# Astable_555_Timer.net
KiCad netlist of a schematic drawn in EAGLE
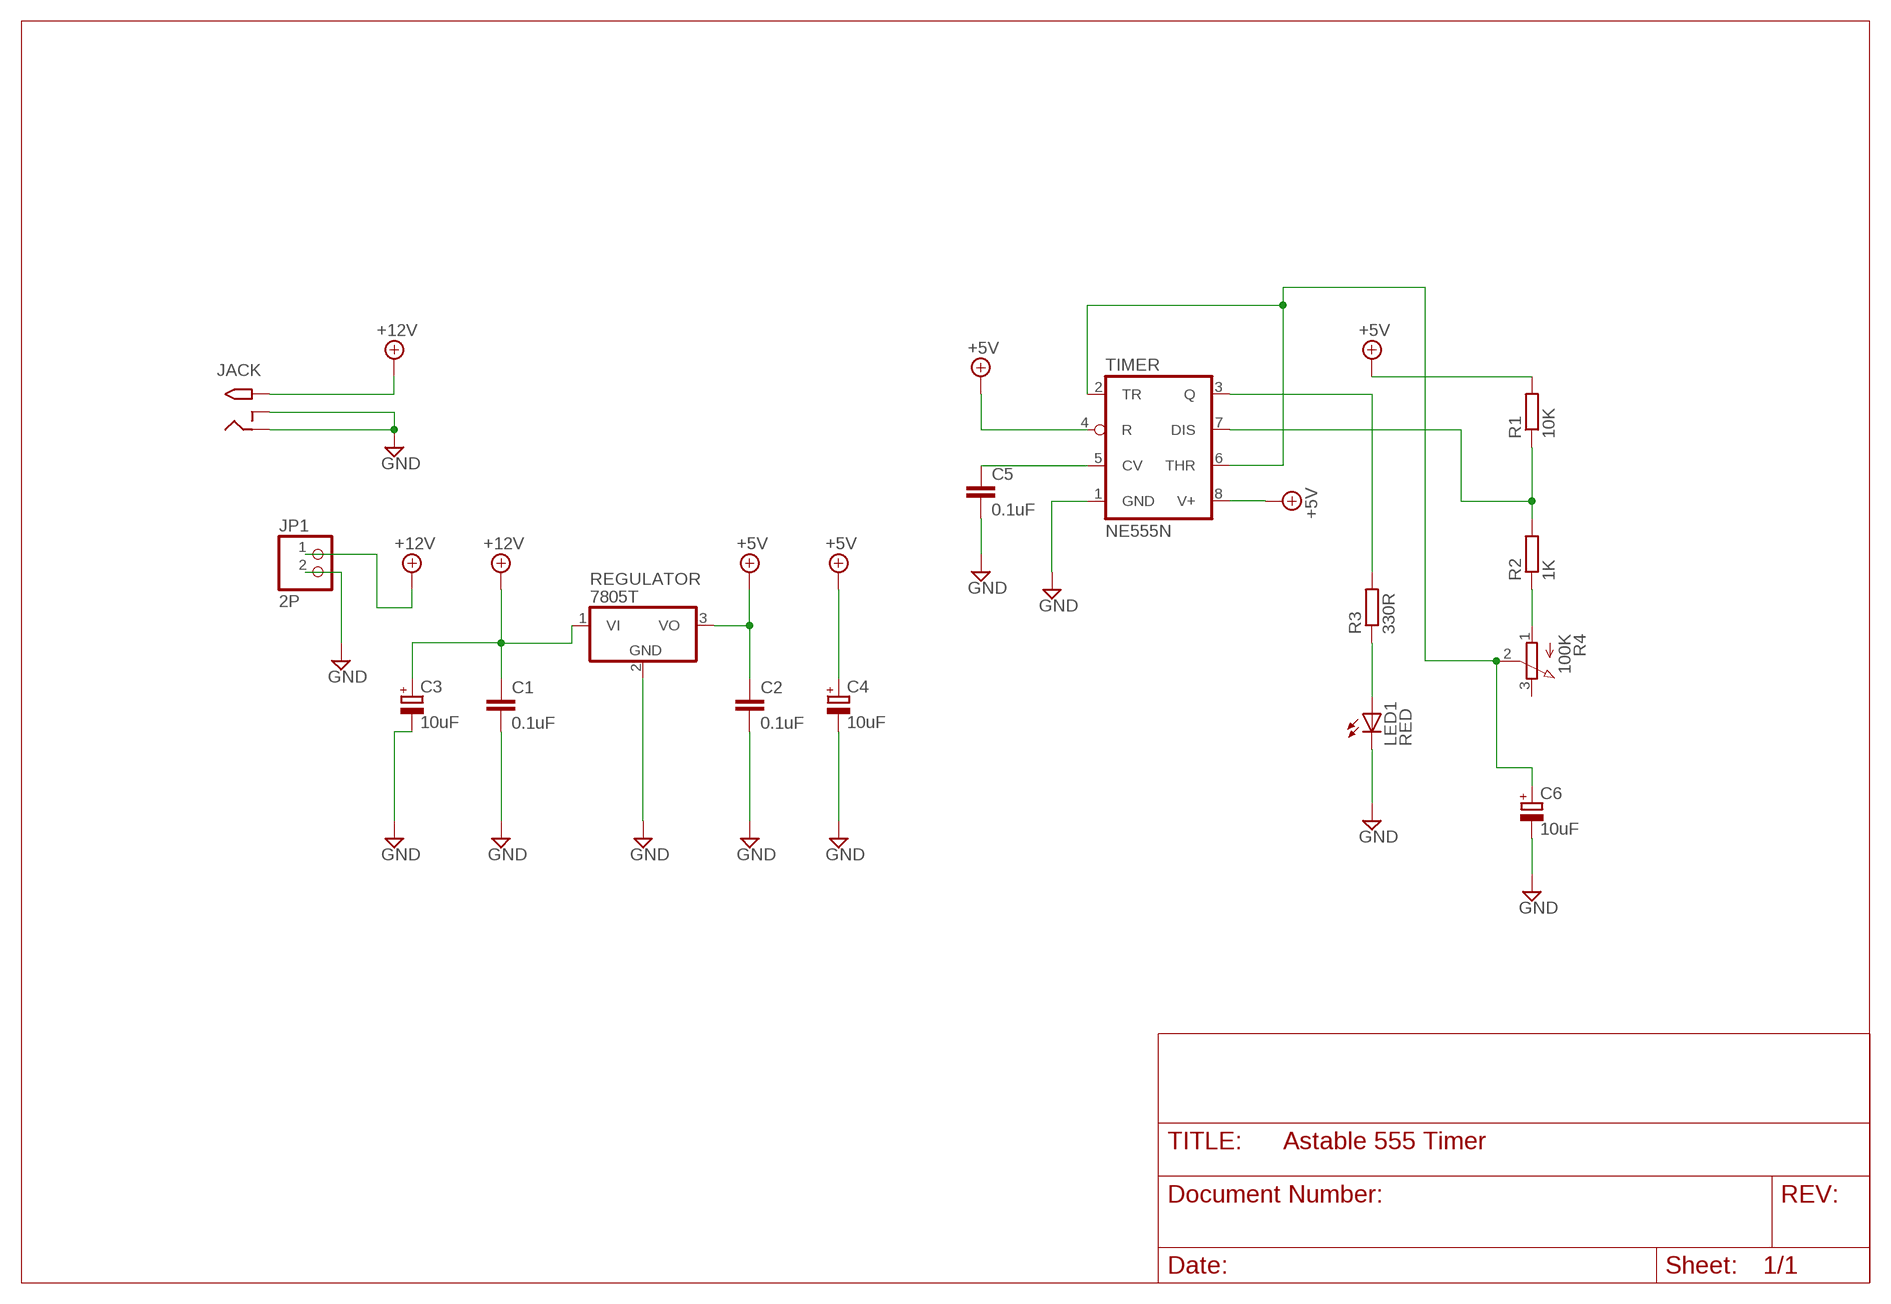
[diagram p0: schematic, sheet 1]

(export (version "E")
  (design (tool "Eeschema 10.0.6"))
  (components
    (comp (ref "C1")
      (value "0.1uF")
      (footprint "eagle-import:C050-035X075")
      (libsource (lib "eagle-import") (part "C-EU050-035X075"))
    )
    (comp (ref "C2")
      (value "0.1uF")
      (footprint "eagle-import:C050-035X075")
      (libsource (lib "eagle-import") (part "C-EU050-035X075"))
    )
    (comp (ref "C3")
      (value "10uF")
      (footprint "eagle-import:E3,5-8")
      (libsource (lib "eagle-import") (part "CPOL-EUE3.5-8"))
    )
    (comp (ref "C4")
      (value "10uF")
      (footprint "eagle-import:E3,5-8")
      (libsource (lib "eagle-import") (part "CPOL-EUE3.5-8"))
    )
    (comp (ref "C5")
      (value "0.1uF")
      (footprint "eagle-import:C050-035X075")
      (libsource (lib "eagle-import") (part "C-EU050-035X075"))
    )
    (comp (ref "C6")
      (value "10uF")
      (footprint "eagle-import:E3,5-8")
      (libsource (lib "eagle-import") (part "CPOL-EUE3.5-8"))
    )
    (comp (ref "JACK")
      (value "2.1MMJACKTHM")
      (footprint "eagle-import:PJ-102A")
      (libsource (lib "eagle-import") (part "2.1MMJACKTHM"))
    )
    (comp (ref "JP1")
      (value "2P")
      (footprint "eagle-import:1X02")
      (libsource (lib "eagle-import") (part "PINHD-1X2"))
    )
    (comp (ref "LED1")
      (value "RED")
      (footprint "eagle-import:LED5MM")
      (libsource (lib "eagle-import") (part "LED5MM"))
    )
    (comp (ref "R1")
      (value "10K")
      (footprint "eagle-import:0207_15")
      (libsource (lib "eagle-import") (part "R-EU_0207/15"))
    )
    (comp (ref "R2")
      (value "1K")
      (footprint "eagle-import:0207_15")
      (libsource (lib "eagle-import") (part "R-EU_0207/15"))
    )
    (comp (ref "R3")
      (value "330R")
      (footprint "eagle-import:0207_15")
      (libsource (lib "eagle-import") (part "R-EU_0207/15"))
    )
    (comp (ref "R4")
      (value "100K")
      (footprint "eagle-import:3RP_1610N")
      (libsource (lib "eagle-import") (part "3RP/1610N"))
    )
    (comp (ref "REGULATOR")
      (value "7805T")
      (footprint "eagle-import:TO220H")
      (libsource (lib "eagle-import") (part "78T05"))
    )
    (comp (ref "TIMER")
      (value "NE555N")
      (footprint "eagle-import:DIL08-ROUND")
      (libsource (lib "eagle-import") (part "555NNE"))
    )
  )
  (nets
    (net (code "1") (name "+5V") (class "Default")
      (node (ref "C2") (pin "1") (pinfunction "1_1") (pintype "passive"))
      (node (ref "C4") (pin "+") (pinfunction "+_+") (pintype "passive"))
      (node (ref "R1") (pin "2") (pinfunction "2_2") (pintype "passive"))
      (node (ref "REGULATOR") (pin "3") (pinfunction "VO_3") (pintype "passive"))
      (node (ref "TIMER") (pin "4") (pinfunction "R_4") (pintype "input"))
      (node (ref "TIMER") (pin "8") (pinfunction "V+_8") (pintype "power_in"))
    )
    (net (code "2") (name "+12V") (class "Default")
      (node (ref "C1") (pin "1") (pinfunction "1_1") (pintype "passive"))
      (node (ref "C3") (pin "+") (pinfunction "+_+") (pintype "passive"))
      (node (ref "JACK") (pin "TIP") (pinfunction "TIP_TIP") (pintype "bidirectional"))
      (node (ref "JP1") (pin "1") (pinfunction "1_1") (pintype "passive"))
      (node (ref "REGULATOR") (pin "1") (pinfunction "VI_1") (pintype "input"))
    )
    (net (code "3") (name "GND") (class "Default")
      (node (ref "C1") (pin "2") (pinfunction "2_2") (pintype "passive"))
      (node (ref "C2") (pin "2") (pinfunction "2_2") (pintype "passive"))
      (node (ref "C3") (pin "-") (pinfunction "-_-") (pintype "passive"))
      (node (ref "C4") (pin "-") (pinfunction "-_-") (pintype "passive"))
      (node (ref "C5") (pin "2") (pinfunction "2_2") (pintype "passive"))
      (node (ref "C6") (pin "-") (pinfunction "-_-") (pintype "passive"))
      (node (ref "JACK") (pin "RING") (pinfunction "RING_RING") (pintype "bidirectional"))
      (node (ref "JACK") (pin "RING_SW") (pinfunction "RING_SW_RING_SW") (pintype "bidirectional"))
      (node (ref "JP1") (pin "2") (pinfunction "2_2") (pintype "passive"))
      (node (ref "LED1") (pin "K") (pinfunction "C_K") (pintype "passive"))
      (node (ref "REGULATOR") (pin "2") (pinfunction "GND_2") (pintype "passive"))
      (node (ref "TIMER") (pin "1") (pinfunction "GND_1") (pintype "power_in"))
    )
    (net (code "4") (name "Net-(LED1-PadA)") (class "Default")
      (node (ref "LED1") (pin "A") (pinfunction "A_A") (pintype "passive"))
      (node (ref "R3") (pin "1") (pinfunction "1_1") (pintype "passive"))
    )
    (net (code "5") (name "Net-(R4-A)") (class "Default")
      (node (ref "R2") (pin "1") (pinfunction "1_1") (pintype "passive"))
      (node (ref "R4") (pin "1") (pinfunction "A_1") (pintype "passive"))
    )
    (net (code "6") (name "Net-(R4-S)") (class "Default")
      (node (ref "C6") (pin "+") (pinfunction "+_+") (pintype "passive"))
      (node (ref "R4") (pin "2") (pinfunction "S_2") (pintype "passive"))
      (node (ref "TIMER") (pin "2") (pinfunction "TR_2") (pintype "input"))
      (node (ref "TIMER") (pin "6") (pinfunction "THR_6") (pintype "input"))
    )
    (net (code "7") (name "Net-(TIMER-CV)") (class "Default")
      (node (ref "C5") (pin "1") (pinfunction "1_1") (pintype "passive"))
      (node (ref "TIMER") (pin "5") (pinfunction "CV_5") (pintype "input"))
    )
    (net (code "8") (name "Net-(TIMER-DIS)") (class "Default")
      (node (ref "R1") (pin "1") (pinfunction "1_1") (pintype "passive"))
      (node (ref "R2") (pin "2") (pinfunction "2_2") (pintype "passive"))
      (node (ref "TIMER") (pin "7") (pinfunction "DIS_7") (pintype "input"))
    )
    (net (code "9") (name "Net-(TIMER-Q)") (class "Default")
      (node (ref "R3") (pin "2") (pinfunction "2_2") (pintype "passive"))
      (node (ref "TIMER") (pin "3") (pinfunction "Q_3") (pintype "output"))
    )
    (net (code "10") (name "unconnected-(R4-E-Pad3)") (class "Default")
      (node (ref "R4") (pin "3") (pinfunction "E_3") (pintype "passive"))
    )
  )
)
